# crz7shlda0.net
KiCad netlist of a schematic drawn in EAGLE
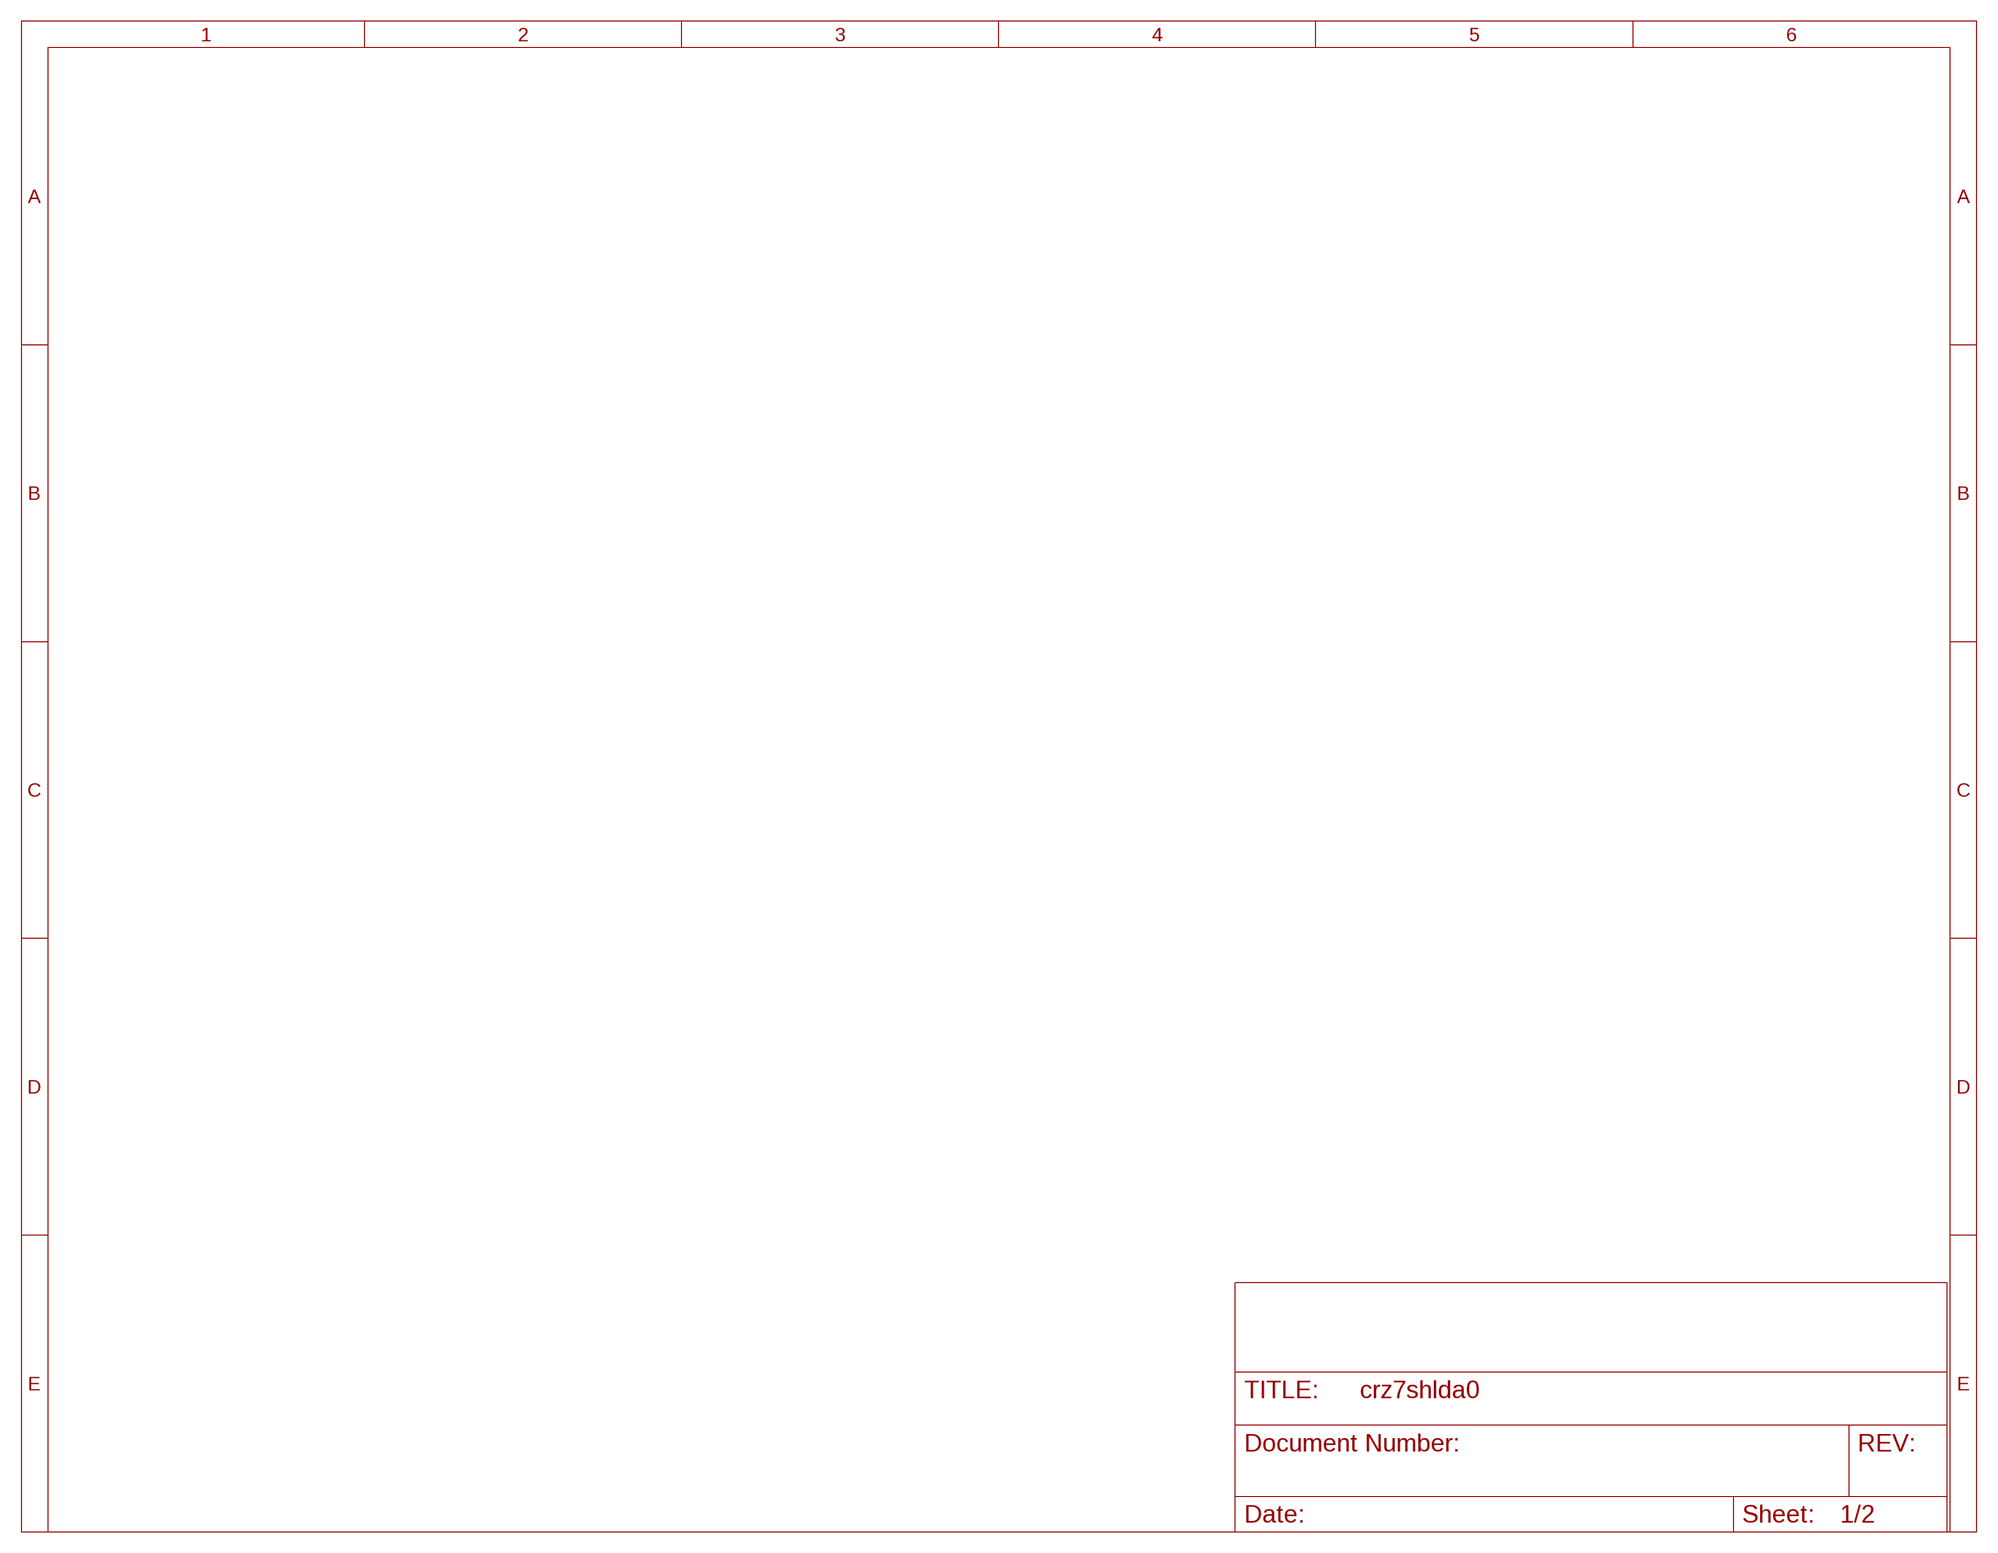
[diagram p0: schematic, sheet 1]
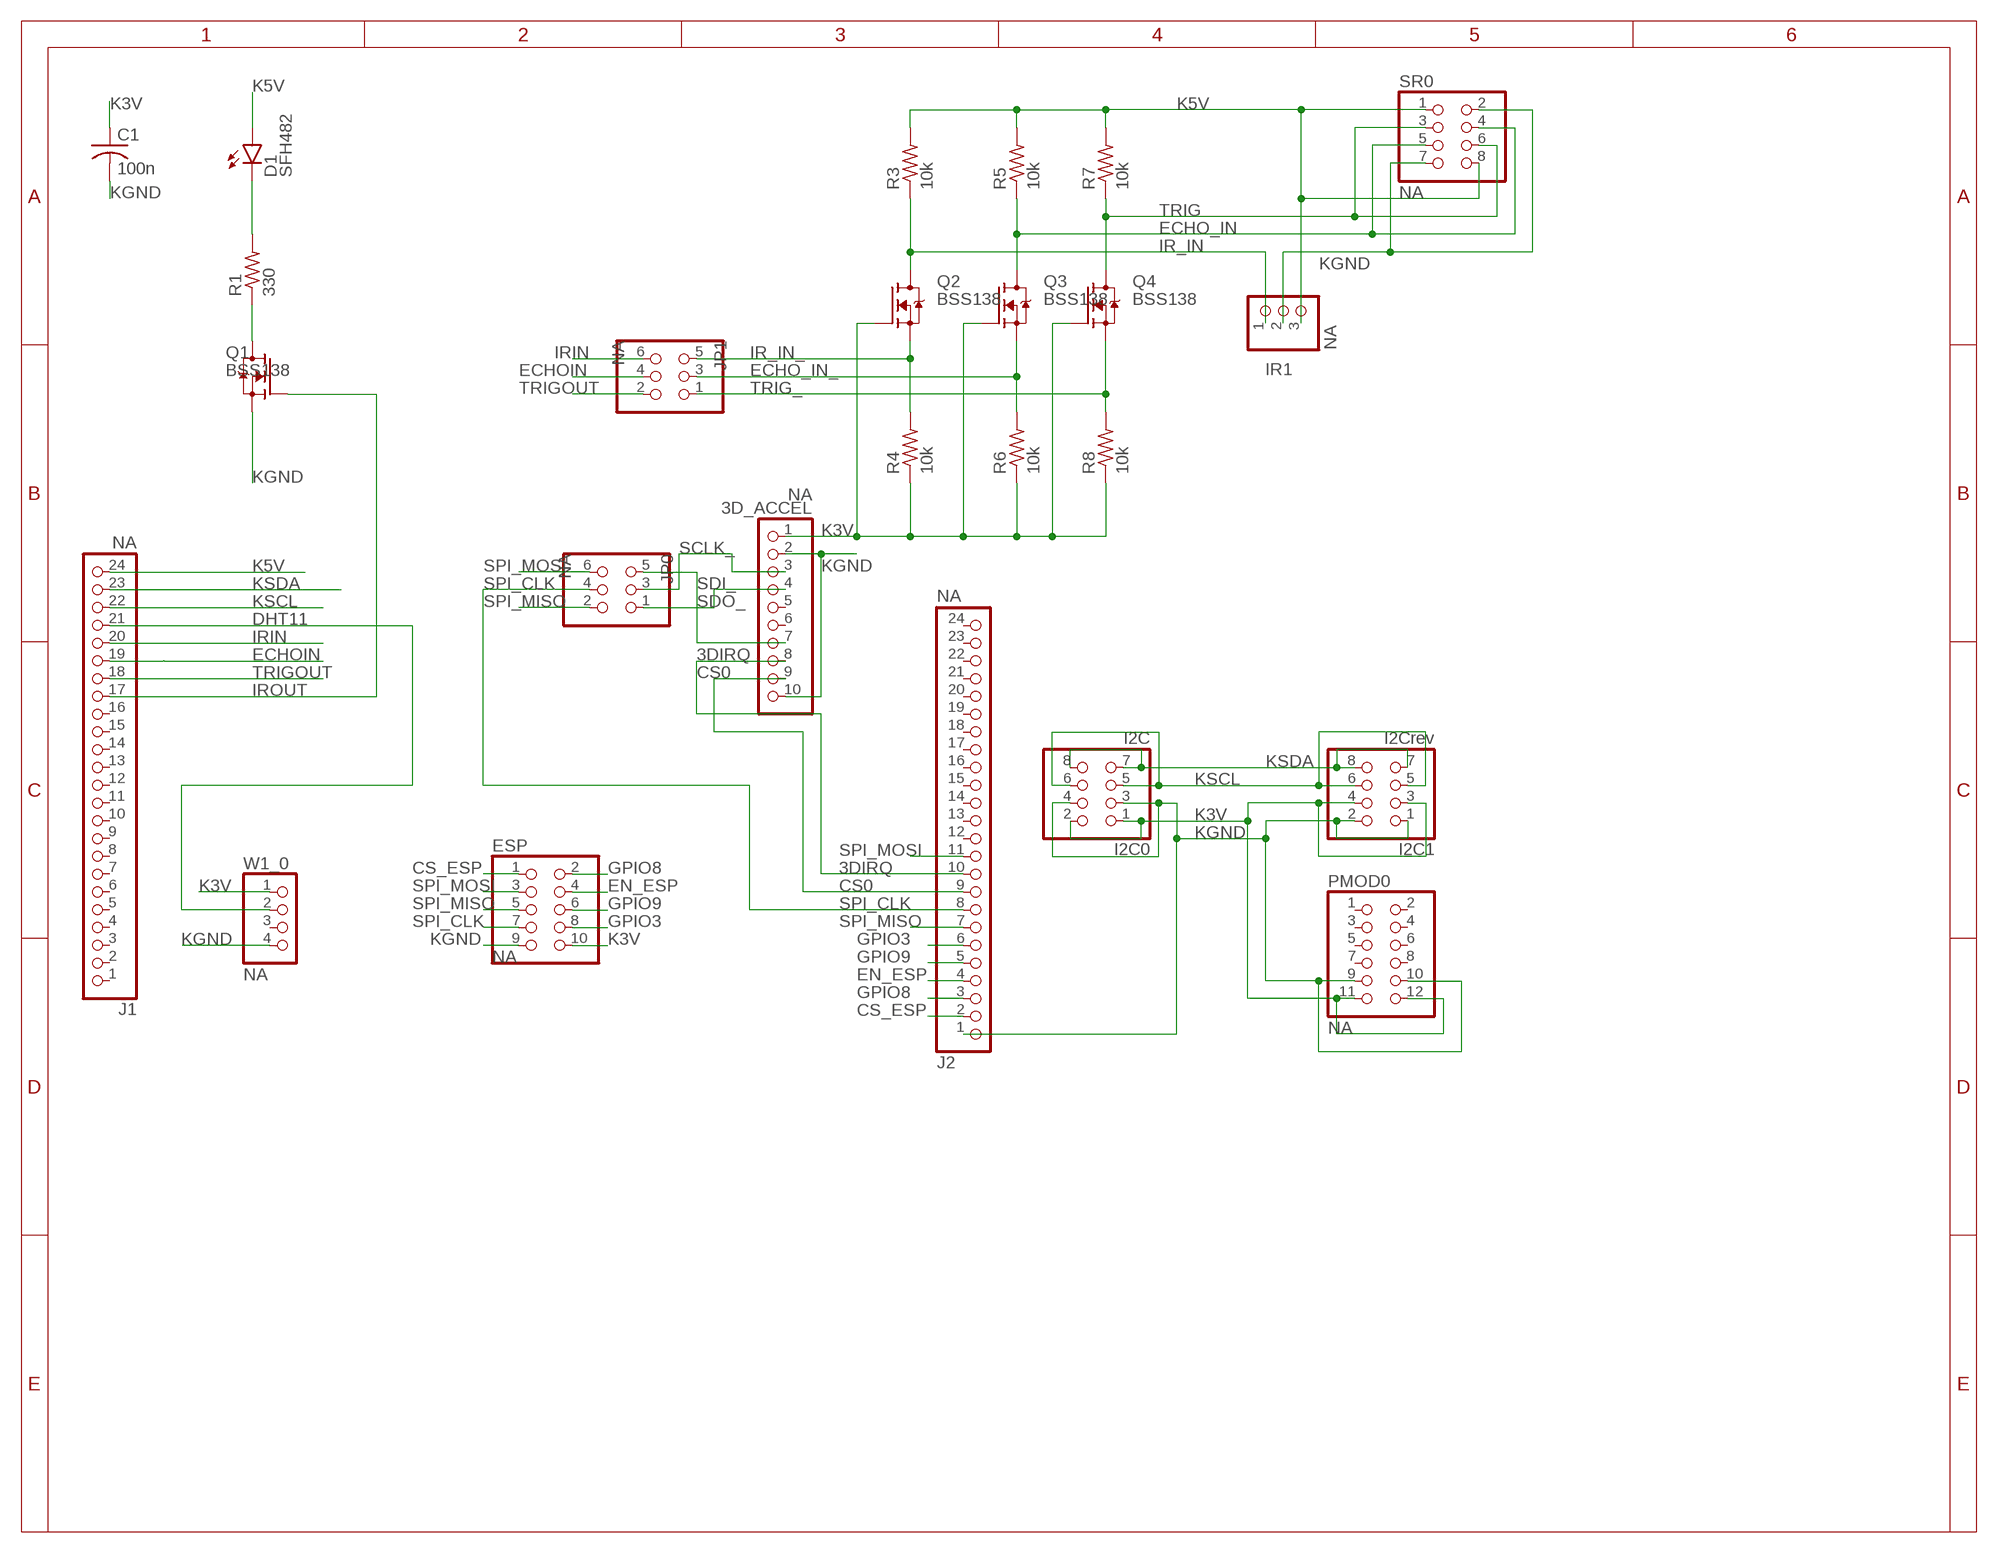
[diagram p1: schematic, sheet 2]

(export (version "E")
  (design (tool "Eeschema 10.0.6"))
  (components
    (comp (ref "3D_ACCEL")
      (value "NA")
      (footprint "eagle-import:1X10")
      (libsource (lib "eagle-import") (part "PINHD-1X10"))
    )
    (comp (ref "C1")
      (value "100n")
      (footprint "eagle-import:C0402")
      (libsource (lib "eagle-import") (part "C-USC0402"))
    )
    (comp (ref "D1")
      (value "SFH482")
      (footprint "eagle-import:SFH482")
      (libsource (lib "eagle-import") (part "SFH482"))
    )
    (comp (ref "ESP")
      (value "NA")
      (footprint "eagle-import:2X05")
      (libsource (lib "eagle-import") (part "PINHD-2X5"))
    )
    (comp (ref "I2C0")
      (value "I2C")
      (footprint "eagle-import:2X04")
      (libsource (lib "eagle-import") (part "PINHD-2X4"))
    )
    (comp (ref "I2C1")
      (value "I2Crev")
      (footprint "eagle-import:2X04")
      (libsource (lib "eagle-import") (part "PINHD-2X4"))
    )
    (comp (ref "IR1")
      (value "NA")
      (footprint "eagle-import:1X03")
      (libsource (lib "eagle-import") (part "PINHD-1X3"))
    )
    (comp (ref "J1")
      (value "NA")
      (footprint "eagle-import:1X24")
      (libsource (lib "eagle-import") (part "PINHD-1X24"))
    )
    (comp (ref "J2")
      (value "NA")
      (footprint "eagle-import:1X24")
      (libsource (lib "eagle-import") (part "PINHD-1X24"))
    )
    (comp (ref "JP0")
      (value "NA")
      (footprint "eagle-import:2X03")
      (libsource (lib "eagle-import") (part "PINHD-2X3"))
    )
    (comp (ref "JP1")
      (value "NA")
      (footprint "eagle-import:2X03")
      (libsource (lib "eagle-import") (part "PINHD-2X3"))
    )
    (comp (ref "PMOD0")
      (value "NA")
      (footprint "eagle-import:2X06")
      (libsource (lib "eagle-import") (part "PINHD-2X6"))
    )
    (comp (ref "Q1")
      (value "BSS138")
      (footprint "eagle-import:SOT23")
      (fields (field (name "MF") "Fairchild"))
      (libsource (lib "eagle-import") (part "BSS138"))
    )
    (comp (ref "Q2")
      (value "BSS138")
      (footprint "eagle-import:SOT23")
      (fields (field (name "MF") "Fairchild"))
      (libsource (lib "eagle-import") (part "BSS138"))
    )
    (comp (ref "Q3")
      (value "BSS138")
      (footprint "eagle-import:SOT23")
      (fields (field (name "MF") "Fairchild"))
      (libsource (lib "eagle-import") (part "BSS138"))
    )
    (comp (ref "Q4")
      (value "BSS138")
      (footprint "eagle-import:SOT23")
      (fields (field (name "MF") "Fairchild"))
      (libsource (lib "eagle-import") (part "BSS138"))
    )
    (comp (ref "R1")
      (value "330")
      (footprint "eagle-import:R0402")
      (libsource (lib "eagle-import") (part "R-US_R0402"))
    )
    (comp (ref "R3")
      (value "10k")
      (footprint "eagle-import:R0402")
      (libsource (lib "eagle-import") (part "R-US_R0402"))
    )
    (comp (ref "R4")
      (value "10k")
      (footprint "eagle-import:R0402")
      (libsource (lib "eagle-import") (part "R-US_R0402"))
    )
    (comp (ref "R5")
      (value "10k")
      (footprint "eagle-import:R0402")
      (libsource (lib "eagle-import") (part "R-US_R0402"))
    )
    (comp (ref "R6")
      (value "10k")
      (footprint "eagle-import:R0402")
      (libsource (lib "eagle-import") (part "R-US_R0402"))
    )
    (comp (ref "R7")
      (value "10k")
      (footprint "eagle-import:R0402")
      (libsource (lib "eagle-import") (part "R-US_R0402"))
    )
    (comp (ref "R8")
      (value "10k")
      (footprint "eagle-import:R0402")
      (libsource (lib "eagle-import") (part "R-US_R0402"))
    )
    (comp (ref "SR0")
      (value "NA")
      (footprint "eagle-import:2X04")
      (libsource (lib "eagle-import") (part "PINHD-2X4"))
    )
    (comp (ref "W1_0")
      (value "NA")
      (footprint "eagle-import:1X04")
      (libsource (lib "eagle-import") (part "PINHD-1X4"))
    )
  )
  (nets
    (net (code "1") (name "3DIRQ") (class "Default")
      (node (ref "3D_ACCEL") (pin "8") (pinfunction "8_8") (pintype "passive"))
      (node (ref "J2") (pin "10") (pinfunction "10_10") (pintype "passive"))
    )
    (net (code "2") (name "CS0") (class "Default")
      (node (ref "3D_ACCEL") (pin "9") (pinfunction "9_9") (pintype "passive"))
      (node (ref "J2") (pin "9") (pinfunction "9_9") (pintype "passive"))
    )
    (net (code "3") (name "CS_ESP") (class "Default")
      (node (ref "ESP") (pin "1") (pinfunction "1_1") (pintype "passive"))
      (node (ref "J2") (pin "2") (pinfunction "2_2") (pintype "passive"))
    )
    (net (code "4") (name "DHT11") (class "Default")
      (node (ref "J1") (pin "21") (pinfunction "21_21") (pintype "passive"))
      (node (ref "W1_0") (pin "2") (pinfunction "2_2") (pintype "passive"))
    )
    (net (code "5") (name "ECHOIN") (class "Default")
      (node (ref "J1") (pin "19") (pinfunction "19_19") (pintype "passive"))
      (node (ref "JP1") (pin "4") (pinfunction "4_4") (pintype "passive"))
    )
    (net (code "6") (name "ECHO_IN") (class "Default")
      (node (ref "Q3") (pin "3") (pinfunction "D_3") (pintype "passive"))
      (node (ref "R5") (pin "1") (pinfunction "1_1") (pintype "passive"))
      (node (ref "SR0") (pin "4") (pinfunction "4_4") (pintype "passive"))
      (node (ref "SR0") (pin "5") (pinfunction "5_5") (pintype "passive"))
    )
    (net (code "7") (name "ECHO_IN_") (class "Default")
      (node (ref "JP1") (pin "3") (pinfunction "3_3") (pintype "passive"))
      (node (ref "Q3") (pin "2") (pinfunction "S_2") (pintype "passive"))
      (node (ref "R6") (pin "2") (pinfunction "2_2") (pintype "passive"))
    )
    (net (code "8") (name "EN_ESP") (class "Default")
      (node (ref "ESP") (pin "4") (pinfunction "4_4") (pintype "passive"))
      (node (ref "J2") (pin "4") (pinfunction "4_4") (pintype "passive"))
    )
    (net (code "9") (name "GPIO3") (class "Default")
      (node (ref "ESP") (pin "8") (pinfunction "8_8") (pintype "passive"))
      (node (ref "J2") (pin "6") (pinfunction "6_6") (pintype "passive"))
    )
    (net (code "10") (name "GPIO8") (class "Default")
      (node (ref "ESP") (pin "2") (pinfunction "2_2") (pintype "passive"))
      (node (ref "J2") (pin "3") (pinfunction "3_3") (pintype "passive"))
    )
    (net (code "11") (name "GPIO9") (class "Default")
      (node (ref "ESP") (pin "6") (pinfunction "6_6") (pintype "passive"))
      (node (ref "J2") (pin "5") (pinfunction "5_5") (pintype "passive"))
    )
    (net (code "12") (name "IRIN") (class "Default")
      (node (ref "J1") (pin "20") (pinfunction "20_20") (pintype "passive"))
      (node (ref "JP1") (pin "6") (pinfunction "6_6") (pintype "passive"))
    )
    (net (code "13") (name "IROUT") (class "Default")
      (node (ref "J1") (pin "17") (pinfunction "17_17") (pintype "passive"))
      (node (ref "Q1") (pin "1") (pinfunction "G_1") (pintype "passive"))
    )
    (net (code "14") (name "IR_IN") (class "Default")
      (node (ref "IR1") (pin "1") (pinfunction "1_1") (pintype "passive"))
      (node (ref "Q2") (pin "3") (pinfunction "D_3") (pintype "passive"))
      (node (ref "R3") (pin "1") (pinfunction "1_1") (pintype "passive"))
    )
    (net (code "15") (name "IR_IN_") (class "Default")
      (node (ref "JP1") (pin "5") (pinfunction "5_5") (pintype "passive"))
      (node (ref "Q2") (pin "2") (pinfunction "S_2") (pintype "passive"))
      (node (ref "R4") (pin "2") (pinfunction "2_2") (pintype "passive"))
    )
    (net (code "16") (name "K3V") (class "Default")
      (node (ref "3D_ACCEL") (pin "1") (pinfunction "1_1") (pintype "passive"))
      (node (ref "C1") (pin "1") (pinfunction "1_1") (pintype "passive"))
      (node (ref "ESP") (pin "10") (pinfunction "10_10") (pintype "passive"))
      (node (ref "I2C0") (pin "1") (pinfunction "1_1") (pintype "passive"))
      (node (ref "I2C0") (pin "2") (pinfunction "2_2") (pintype "passive"))
      (node (ref "I2C1") (pin "3") (pinfunction "3_3") (pintype "passive"))
      (node (ref "I2C1") (pin "4") (pinfunction "4_4") (pintype "passive"))
      (node (ref "PMOD0") (pin "11") (pinfunction "11_11") (pintype "passive"))
      (node (ref "PMOD0") (pin "12") (pinfunction "12_12") (pintype "passive"))
      (node (ref "Q2") (pin "1") (pinfunction "G_1") (pintype "passive"))
      (node (ref "Q3") (pin "1") (pinfunction "G_1") (pintype "passive"))
      (node (ref "Q4") (pin "1") (pinfunction "G_1") (pintype "passive"))
      (node (ref "R4") (pin "1") (pinfunction "1_1") (pintype "passive"))
      (node (ref "R6") (pin "1") (pinfunction "1_1") (pintype "passive"))
      (node (ref "R8") (pin "1") (pinfunction "1_1") (pintype "passive"))
      (node (ref "W1_0") (pin "1") (pinfunction "1_1") (pintype "passive"))
    )
    (net (code "17") (name "K5V") (class "Default")
      (node (ref "D1") (pin "A") (pinfunction "A_A") (pintype "passive"))
      (node (ref "IR1") (pin "3") (pinfunction "3_3") (pintype "passive"))
      (node (ref "J1") (pin "24") (pinfunction "24_24") (pintype "passive"))
      (node (ref "R3") (pin "2") (pinfunction "2_2") (pintype "passive"))
      (node (ref "R5") (pin "2") (pinfunction "2_2") (pintype "passive"))
      (node (ref "R7") (pin "2") (pinfunction "2_2") (pintype "passive"))
      (node (ref "SR0") (pin "1") (pinfunction "1_1") (pintype "passive"))
      (node (ref "SR0") (pin "8") (pinfunction "8_8") (pintype "passive"))
    )
    (net (code "18") (name "KGND") (class "Default")
      (node (ref "3D_ACCEL") (pin "10") (pinfunction "10_10") (pintype "passive"))
      (node (ref "3D_ACCEL") (pin "2") (pinfunction "2_2") (pintype "passive"))
      (node (ref "C1") (pin "2") (pinfunction "2_2") (pintype "passive"))
      (node (ref "ESP") (pin "9") (pinfunction "9_9") (pintype "passive"))
      (node (ref "I2C0") (pin "3") (pinfunction "3_3") (pintype "passive"))
      (node (ref "I2C0") (pin "4") (pinfunction "4_4") (pintype "passive"))
      (node (ref "I2C1") (pin "1") (pinfunction "1_1") (pintype "passive"))
      (node (ref "I2C1") (pin "2") (pinfunction "2_2") (pintype "passive"))
      (node (ref "IR1") (pin "2") (pinfunction "2_2") (pintype "passive"))
      (node (ref "J2") (pin "1") (pinfunction "1_1") (pintype "passive"))
      (node (ref "PMOD0") (pin "10") (pinfunction "10_10") (pintype "passive"))
      (node (ref "PMOD0") (pin "9") (pinfunction "9_9") (pintype "passive"))
      (node (ref "Q1") (pin "2") (pinfunction "S_2") (pintype "passive"))
      (node (ref "SR0") (pin "2") (pinfunction "2_2") (pintype "passive"))
      (node (ref "SR0") (pin "7") (pinfunction "7_7") (pintype "passive"))
      (node (ref "W1_0") (pin "4") (pinfunction "4_4") (pintype "passive"))
    )
    (net (code "19") (name "KSCL") (class "Default")
      (node (ref "I2C0") (pin "5") (pinfunction "5_5") (pintype "passive"))
      (node (ref "I2C0") (pin "6") (pinfunction "6_6") (pintype "passive"))
      (node (ref "I2C1") (pin "5") (pinfunction "5_5") (pintype "passive"))
      (node (ref "I2C1") (pin "6") (pinfunction "6_6") (pintype "passive"))
      (node (ref "J1") (pin "22") (pinfunction "22_22") (pintype "passive"))
    )
    (net (code "20") (name "KSDA") (class "Default")
      (node (ref "I2C0") (pin "7") (pinfunction "7_7") (pintype "passive"))
      (node (ref "I2C0") (pin "8") (pinfunction "8_8") (pintype "passive"))
      (node (ref "I2C1") (pin "7") (pinfunction "7_7") (pintype "passive"))
      (node (ref "I2C1") (pin "8") (pinfunction "8_8") (pintype "passive"))
      (node (ref "J1") (pin "23") (pinfunction "23_23") (pintype "passive"))
    )
    (net (code "21") (name "Net-(D1-C)") (class "Default")
      (node (ref "D1") (pin "K") (pinfunction "C_K") (pintype "passive"))
      (node (ref "R1") (pin "2") (pinfunction "2_2") (pintype "passive"))
    )
    (net (code "22") (name "Net-(Q1-D)") (class "Default")
      (node (ref "Q1") (pin "3") (pinfunction "D_3") (pintype "passive"))
      (node (ref "R1") (pin "1") (pinfunction "1_1") (pintype "passive"))
    )
    (net (code "23") (name "SCLK_") (class "Default")
      (node (ref "3D_ACCEL") (pin "3") (pinfunction "3_3") (pintype "passive"))
      (node (ref "JP0") (pin "3") (pinfunction "3_3") (pintype "passive"))
    )
    (net (code "24") (name "SDI_") (class "Default")
      (node (ref "3D_ACCEL") (pin "4") (pinfunction "4_4") (pintype "passive"))
      (node (ref "JP0") (pin "1") (pinfunction "1_1") (pintype "passive"))
    )
    (net (code "25") (name "SDO_") (class "Default")
      (node (ref "3D_ACCEL") (pin "7") (pinfunction "7_7") (pintype "passive"))
      (node (ref "JP0") (pin "5") (pinfunction "5_5") (pintype "passive"))
    )
    (net (code "26") (name "SPI_CLK") (class "Default")
      (node (ref "ESP") (pin "7") (pinfunction "7_7") (pintype "passive"))
      (node (ref "J2") (pin "8") (pinfunction "8_8") (pintype "passive"))
      (node (ref "JP0") (pin "4") (pinfunction "4_4") (pintype "passive"))
    )
    (net (code "27") (name "SPI_MISO") (class "Default")
      (node (ref "ESP") (pin "5") (pinfunction "5_5") (pintype "passive"))
      (node (ref "J2") (pin "7") (pinfunction "7_7") (pintype "passive"))
      (node (ref "JP0") (pin "2") (pinfunction "2_2") (pintype "passive"))
    )
    (net (code "28") (name "SPI_MOSI") (class "Default")
      (node (ref "ESP") (pin "3") (pinfunction "3_3") (pintype "passive"))
      (node (ref "J2") (pin "11") (pinfunction "11_11") (pintype "passive"))
      (node (ref "JP0") (pin "6") (pinfunction "6_6") (pintype "passive"))
    )
    (net (code "29") (name "TRIG") (class "Default")
      (node (ref "Q4") (pin "3") (pinfunction "D_3") (pintype "passive"))
      (node (ref "R7") (pin "1") (pinfunction "1_1") (pintype "passive"))
      (node (ref "SR0") (pin "3") (pinfunction "3_3") (pintype "passive"))
      (node (ref "SR0") (pin "6") (pinfunction "6_6") (pintype "passive"))
    )
    (net (code "30") (name "TRIGOUT") (class "Default")
      (node (ref "J1") (pin "18") (pinfunction "18_18") (pintype "passive"))
      (node (ref "JP1") (pin "2") (pinfunction "2_2") (pintype "passive"))
    )
    (net (code "31") (name "TRIG_") (class "Default")
      (node (ref "JP1") (pin "1") (pinfunction "1_1") (pintype "passive"))
      (node (ref "Q4") (pin "2") (pinfunction "S_2") (pintype "passive"))
      (node (ref "R8") (pin "2") (pinfunction "2_2") (pintype "passive"))
    )
    (net (code "32") (name "unconnected-(3D_ACCEL-Pad5)") (class "Default")
      (node (ref "3D_ACCEL") (pin "5") (pinfunction "5_5") (pintype "passive"))
    )
    (net (code "33") (name "unconnected-(3D_ACCEL-Pad6)") (class "Default")
      (node (ref "3D_ACCEL") (pin "6") (pinfunction "6_6") (pintype "passive"))
    )
    (net (code "34") (name "unconnected-(J1-Pad1)") (class "Default")
      (node (ref "J1") (pin "1") (pinfunction "1_1") (pintype "passive"))
    )
    (net (code "35") (name "unconnected-(J1-Pad2)") (class "Default")
      (node (ref "J1") (pin "2") (pinfunction "2_2") (pintype "passive"))
    )
    (net (code "36") (name "unconnected-(J1-Pad3)") (class "Default")
      (node (ref "J1") (pin "3") (pinfunction "3_3") (pintype "passive"))
    )
    (net (code "37") (name "unconnected-(J1-Pad4)") (class "Default")
      (node (ref "J1") (pin "4") (pinfunction "4_4") (pintype "passive"))
    )
    (net (code "38") (name "unconnected-(J1-Pad5)") (class "Default")
      (node (ref "J1") (pin "5") (pinfunction "5_5") (pintype "passive"))
    )
    (net (code "39") (name "unconnected-(J1-Pad6)") (class "Default")
      (node (ref "J1") (pin "6") (pinfunction "6_6") (pintype "passive"))
    )
    (net (code "40") (name "unconnected-(J1-Pad7)") (class "Default")
      (node (ref "J1") (pin "7") (pinfunction "7_7") (pintype "passive"))
    )
    (net (code "41") (name "unconnected-(J1-Pad8)") (class "Default")
      (node (ref "J1") (pin "8") (pinfunction "8_8") (pintype "passive"))
    )
    (net (code "42") (name "unconnected-(J1-Pad9)") (class "Default")
      (node (ref "J1") (pin "9") (pinfunction "9_9") (pintype "passive"))
    )
    (net (code "43") (name "unconnected-(J1-Pad10)") (class "Default")
      (node (ref "J1") (pin "10") (pinfunction "10_10") (pintype "passive"))
    )
    (net (code "44") (name "unconnected-(J1-Pad11)") (class "Default")
      (node (ref "J1") (pin "11") (pinfunction "11_11") (pintype "passive"))
    )
    (net (code "45") (name "unconnected-(J1-Pad12)") (class "Default")
      (node (ref "J1") (pin "12") (pinfunction "12_12") (pintype "passive"))
    )
    (net (code "46") (name "unconnected-(J1-Pad13)") (class "Default")
      (node (ref "J1") (pin "13") (pinfunction "13_13") (pintype "passive"))
    )
    (net (code "47") (name "unconnected-(J1-Pad14)") (class "Default")
      (node (ref "J1") (pin "14") (pinfunction "14_14") (pintype "passive"))
    )
    (net (code "48") (name "unconnected-(J1-Pad15)") (class "Default")
      (node (ref "J1") (pin "15") (pinfunction "15_15") (pintype "passive"))
    )
    (net (code "49") (name "unconnected-(J1-Pad16)") (class "Default")
      (node (ref "J1") (pin "16") (pinfunction "16_16") (pintype "passive"))
    )
    (net (code "50") (name "unconnected-(J2-Pad12)") (class "Default")
      (node (ref "J2") (pin "12") (pinfunction "12_12") (pintype "passive"))
    )
    (net (code "51") (name "unconnected-(J2-Pad13)") (class "Default")
      (node (ref "J2") (pin "13") (pinfunction "13_13") (pintype "passive"))
    )
    (net (code "52") (name "unconnected-(J2-Pad14)") (class "Default")
      (node (ref "J2") (pin "14") (pinfunction "14_14") (pintype "passive"))
    )
    (net (code "53") (name "unconnected-(J2-Pad15)") (class "Default")
      (node (ref "J2") (pin "15") (pinfunction "15_15") (pintype "passive"))
    )
    (net (code "54") (name "unconnected-(J2-Pad16)") (class "Default")
      (node (ref "J2") (pin "16") (pinfunction "16_16") (pintype "passive"))
    )
    (net (code "55") (name "unconnected-(J2-Pad17)") (class "Default")
      (node (ref "J2") (pin "17") (pinfunction "17_17") (pintype "passive"))
    )
    (net (code "56") (name "unconnected-(J2-Pad18)") (class "Default")
      (node (ref "J2") (pin "18") (pinfunction "18_18") (pintype "passive"))
    )
    (net (code "57") (name "unconnected-(J2-Pad19)") (class "Default")
      (node (ref "J2") (pin "19") (pinfunction "19_19") (pintype "passive"))
    )
    (net (code "58") (name "unconnected-(J2-Pad20)") (class "Default")
      (node (ref "J2") (pin "20") (pinfunction "20_20") (pintype "passive"))
    )
    (net (code "59") (name "unconnected-(J2-Pad21)") (class "Default")
      (node (ref "J2") (pin "21") (pinfunction "21_21") (pintype "passive"))
    )
    (net (code "60") (name "unconnected-(J2-Pad22)") (class "Default")
      (node (ref "J2") (pin "22") (pinfunction "22_22") (pintype "passive"))
    )
    (net (code "61") (name "unconnected-(J2-Pad23)") (class "Default")
      (node (ref "J2") (pin "23") (pinfunction "23_23") (pintype "passive"))
    )
    (net (code "62") (name "unconnected-(J2-Pad24)") (class "Default")
      (node (ref "J2") (pin "24") (pinfunction "24_24") (pintype "passive"))
    )
    (net (code "63") (name "unconnected-(PMOD0-Pad1)") (class "Default")
      (node (ref "PMOD0") (pin "1") (pinfunction "1_1") (pintype "passive"))
    )
    (net (code "64") (name "unconnected-(PMOD0-Pad2)") (class "Default")
      (node (ref "PMOD0") (pin "2") (pinfunction "2_2") (pintype "passive"))
    )
    (net (code "65") (name "unconnected-(PMOD0-Pad3)") (class "Default")
      (node (ref "PMOD0") (pin "3") (pinfunction "3_3") (pintype "passive"))
    )
    (net (code "66") (name "unconnected-(PMOD0-Pad4)") (class "Default")
      (node (ref "PMOD0") (pin "4") (pinfunction "4_4") (pintype "passive"))
    )
    (net (code "67") (name "unconnected-(PMOD0-Pad5)") (class "Default")
      (node (ref "PMOD0") (pin "5") (pinfunction "5_5") (pintype "passive"))
    )
    (net (code "68") (name "unconnected-(PMOD0-Pad6)") (class "Default")
      (node (ref "PMOD0") (pin "6") (pinfunction "6_6") (pintype "passive"))
    )
    (net (code "69") (name "unconnected-(PMOD0-Pad7)") (class "Default")
      (node (ref "PMOD0") (pin "7") (pinfunction "7_7") (pintype "passive"))
    )
    (net (code "70") (name "unconnected-(PMOD0-Pad8)") (class "Default")
      (node (ref "PMOD0") (pin "8") (pinfunction "8_8") (pintype "passive"))
    )
    (net (code "71") (name "unconnected-(W1_0-Pad3)") (class "Default")
      (node (ref "W1_0") (pin "3") (pinfunction "3_3") (pintype "passive"))
    )
  )
)
